# tsl-bt-shield.net
KiCad netlist of a schematic drawn in EAGLE
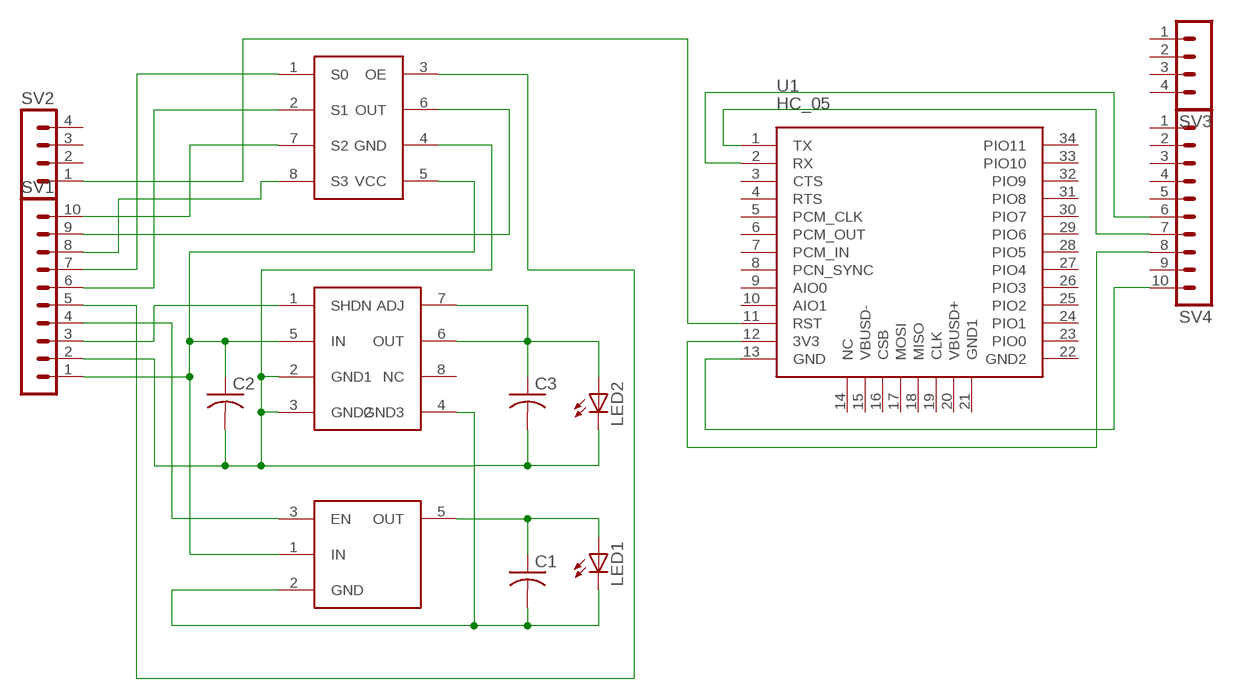
[diagram p0: schematic, sheet 1]

(export (version "E")
  (design (tool "Eeschema 10.0.6"))
  (components
    (comp (ref "C1")
      (value "C-USC1206K")
      (footprint "eagle-import:C1206K")
      (libsource (lib "eagle-import") (part "C-USC1206K"))
    )
    (comp (ref "C2")
      (value "C-USC1206K")
      (footprint "eagle-import:C1206K")
      (libsource (lib "eagle-import") (part "C-USC1206K"))
    )
    (comp (ref "C3")
      (value "C-USC1206K")
      (footprint "eagle-import:C1206K")
      (libsource (lib "eagle-import") (part "C-USC1206K"))
    )
    (comp (ref "LED1")
      (value "LED")
      (footprint "eagle-import:SMARTLED-TTW")
      (libsource (lib "eagle-import") (part "LED"))
    )
    (comp (ref "LED2")
      (value "LED")
      (footprint "eagle-import:SMARTLED-TTW")
      (libsource (lib "eagle-import") (part "LED"))
    )
    (comp (ref "SV1")
      (value "MA10-1")
      (footprint "eagle-import:MA10-1")
      (libsource (lib "eagle-import") (part "MA10-1"))
    )
    (comp (ref "SV2")
      (value "MA04-1")
      (footprint "eagle-import:MA04-1")
      (libsource (lib "eagle-import") (part "MA04-1"))
    )
    (comp (ref "SV3")
      (value "MA04-1")
      (footprint "eagle-import:MA04-1")
      (libsource (lib "eagle-import") (part "MA04-1"))
    )
    (comp (ref "SV4")
      (value "MA10-1")
      (footprint "eagle-import:MA10-1")
      (libsource (lib "eagle-import") (part "MA10-1"))
    )
    (comp (ref "U$1")
      (value "LT3008")
      (footprint "eagle-import:SOT23-8")
      (libsource (lib "eagle-import") (part "LT3008"))
    )
    (comp (ref "U$2")
      (value "TPS7701")
      (footprint "eagle-import:SOT23-5")
      (libsource (lib "eagle-import") (part "TPS7701"))
    )
    (comp (ref "U$3")
      (value "TSL230")
      (footprint "eagle-import:TSL230-SOIC")
      (libsource (lib "eagle-import") (part "TSL230"))
    )
    (comp (ref "U1")
      (value "HC_05")
      (footprint "eagle-import:BLUETOOTH_SMD")
      (libsource (lib "eagle-import") (part "HC_05"))
    )
  )
  (nets
    (net (code "1") (name "Net-(LED1-A)") (class "Default")
      (node (ref "C1") (pin "1") (pinfunction "1_1") (pintype "passive"))
      (node (ref "LED1") (pin "A@1") (pinfunction "A_A@1") (pintype "passive"))
      (node (ref "U$2") (pin "5") (pinfunction "OUT_5") (pintype "bidirectional"))
    )
    (net (code "2") (name "Net-(LED1-C)") (class "Default")
      (node (ref "C1") (pin "2") (pinfunction "2_2") (pintype "passive"))
      (node (ref "C2") (pin "2") (pinfunction "2_2") (pintype "passive"))
      (node (ref "C3") (pin "2") (pinfunction "2_2") (pintype "passive"))
      (node (ref "LED1") (pin "C@1") (pinfunction "C_C@1") (pintype "passive"))
      (node (ref "LED2") (pin "C@1") (pinfunction "C_C@1") (pintype "passive"))
      (node (ref "SV1") (pin "2") (pinfunction "2_2") (pintype "passive"))
      (node (ref "U$1") (pin "2") (pinfunction "GND1_2") (pintype "bidirectional"))
      (node (ref "U$1") (pin "3") (pinfunction "GND2_3") (pintype "bidirectional"))
      (node (ref "U$1") (pin "4") (pinfunction "GND3_4") (pintype "bidirectional"))
      (node (ref "U$2") (pin "2") (pinfunction "GND_2") (pintype "bidirectional"))
      (node (ref "U$3") (pin "4") (pinfunction "GND_4") (pintype "bidirectional"))
    )
    (net (code "3") (name "Net-(LED2-A)") (class "Default")
      (node (ref "C3") (pin "1") (pinfunction "1_1") (pintype "passive"))
      (node (ref "LED2") (pin "A@1") (pinfunction "A_A@1") (pintype "passive"))
      (node (ref "U$1") (pin "6") (pinfunction "OUT_6") (pintype "bidirectional"))
      (node (ref "U$1") (pin "7") (pinfunction "ADJ_7") (pintype "bidirectional"))
    )
    (net (code "4") (name "Net-(U$1-IN)") (class "Default")
      (node (ref "C2") (pin "1") (pinfunction "1_1") (pintype "passive"))
      (node (ref "SV1") (pin "1") (pinfunction "1_1") (pintype "passive"))
      (node (ref "U$1") (pin "5") (pinfunction "IN_5") (pintype "bidirectional"))
      (node (ref "U$2") (pin "1") (pinfunction "IN_1") (pintype "bidirectional"))
      (node (ref "U$3") (pin "5") (pinfunction "VCC_5") (pintype "bidirectional"))
    )
    (net (code "5") (name "Net-(U$1-SHDN)") (class "Default")
      (node (ref "SV1") (pin "3") (pinfunction "3_3") (pintype "passive"))
      (node (ref "U$1") (pin "1") (pinfunction "SHDN_1") (pintype "bidirectional"))
    )
    (net (code "6") (name "Net-(U$2-EN)") (class "Default")
      (node (ref "SV1") (pin "4") (pinfunction "4_4") (pintype "passive"))
      (node (ref "U$2") (pin "3") (pinfunction "EN_3") (pintype "bidirectional"))
    )
    (net (code "7") (name "Net-(U$3-OE)") (class "Default")
      (node (ref "SV1") (pin "5") (pinfunction "5_5") (pintype "passive"))
      (node (ref "U$3") (pin "3") (pinfunction "OE_3") (pintype "bidirectional"))
    )
    (net (code "8") (name "Net-(U$3-OUT)") (class "Default")
      (node (ref "SV1") (pin "9") (pinfunction "9_9") (pintype "passive"))
      (node (ref "U$3") (pin "6") (pinfunction "OUT_6") (pintype "bidirectional"))
    )
    (net (code "9") (name "Net-(U$3-S0)") (class "Default")
      (node (ref "SV1") (pin "7") (pinfunction "7_7") (pintype "passive"))
      (node (ref "U$3") (pin "1") (pinfunction "S0_1") (pintype "bidirectional"))
    )
    (net (code "10") (name "Net-(U$3-S1)") (class "Default")
      (node (ref "SV1") (pin "6") (pinfunction "6_6") (pintype "passive"))
      (node (ref "U$3") (pin "2") (pinfunction "S1_2") (pintype "bidirectional"))
    )
    (net (code "11") (name "Net-(U$3-S2)") (class "Default")
      (node (ref "SV1") (pin "10") (pinfunction "10_10") (pintype "passive"))
      (node (ref "U$3") (pin "7") (pinfunction "S2_7") (pintype "bidirectional"))
    )
    (net (code "12") (name "Net-(U$3-S3)") (class "Default")
      (node (ref "SV1") (pin "8") (pinfunction "8_8") (pintype "passive"))
      (node (ref "U$3") (pin "8") (pinfunction "S3_8") (pintype "bidirectional"))
    )
    (net (code "13") (name "Net-(U1-3V3)") (class "Default")
      (node (ref "SV4") (pin "8") (pinfunction "8_8") (pintype "passive"))
      (node (ref "U1") (pin "12") (pinfunction "3V3_12") (pintype "bidirectional"))
    )
    (net (code "14") (name "Net-(U1-GND)") (class "Default")
      (node (ref "SV4") (pin "10") (pinfunction "10_10") (pintype "passive"))
      (node (ref "U1") (pin "13") (pinfunction "GND_13") (pintype "bidirectional"))
    )
    (net (code "15") (name "Net-(U1-RST)") (class "Default")
      (node (ref "SV2") (pin "1") (pinfunction "1_1") (pintype "passive"))
      (node (ref "U1") (pin "11") (pinfunction "RST_11") (pintype "bidirectional"))
    )
    (net (code "16") (name "Net-(U1-RX)") (class "Default")
      (node (ref "SV4") (pin "6") (pinfunction "6_6") (pintype "passive"))
      (node (ref "U1") (pin "2") (pinfunction "RX_2") (pintype "bidirectional"))
    )
    (net (code "17") (name "Net-(U1-TX)") (class "Default")
      (node (ref "SV4") (pin "7") (pinfunction "7_7") (pintype "passive"))
      (node (ref "U1") (pin "1") (pinfunction "TX_1") (pintype "bidirectional"))
    )
    (net (code "18") (name "unconnected-(SV2-Pad2)") (class "Default")
      (node (ref "SV2") (pin "2") (pinfunction "2_2") (pintype "passive"))
    )
    (net (code "19") (name "unconnected-(SV2-Pad3)") (class "Default")
      (node (ref "SV2") (pin "3") (pinfunction "3_3") (pintype "passive"))
    )
    (net (code "20") (name "unconnected-(SV2-Pad4)") (class "Default")
      (node (ref "SV2") (pin "4") (pinfunction "4_4") (pintype "passive"))
    )
    (net (code "21") (name "unconnected-(SV3-Pad1)") (class "Default")
      (node (ref "SV3") (pin "1") (pinfunction "1_1") (pintype "passive"))
    )
    (net (code "22") (name "unconnected-(SV3-Pad2)") (class "Default")
      (node (ref "SV3") (pin "2") (pinfunction "2_2") (pintype "passive"))
    )
    (net (code "23") (name "unconnected-(SV3-Pad3)") (class "Default")
      (node (ref "SV3") (pin "3") (pinfunction "3_3") (pintype "passive"))
    )
    (net (code "24") (name "unconnected-(SV3-Pad4)") (class "Default")
      (node (ref "SV3") (pin "4") (pinfunction "4_4") (pintype "passive"))
    )
    (net (code "25") (name "unconnected-(SV4-Pad1)") (class "Default")
      (node (ref "SV4") (pin "1") (pinfunction "1_1") (pintype "passive"))
    )
    (net (code "26") (name "unconnected-(SV4-Pad2)") (class "Default")
      (node (ref "SV4") (pin "2") (pinfunction "2_2") (pintype "passive"))
    )
    (net (code "27") (name "unconnected-(SV4-Pad3)") (class "Default")
      (node (ref "SV4") (pin "3") (pinfunction "3_3") (pintype "passive"))
    )
    (net (code "28") (name "unconnected-(SV4-Pad4)") (class "Default")
      (node (ref "SV4") (pin "4") (pinfunction "4_4") (pintype "passive"))
    )
    (net (code "29") (name "unconnected-(SV4-Pad5)") (class "Default")
      (node (ref "SV4") (pin "5") (pinfunction "5_5") (pintype "passive"))
    )
    (net (code "30") (name "unconnected-(SV4-Pad9)") (class "Default")
      (node (ref "SV4") (pin "9") (pinfunction "9_9") (pintype "passive"))
    )
    (net (code "31") (name "unconnected-(U$1-NC-Pad8)") (class "Default")
      (node (ref "U$1") (pin "8") (pinfunction "NC_8") (pintype "bidirectional"))
    )
    (net (code "32") (name "unconnected-(U1-AIO0-Pad9)") (class "Default")
      (node (ref "U1") (pin "9") (pinfunction "AIO0_9") (pintype "bidirectional"))
    )
    (net (code "33") (name "unconnected-(U1-AIO1-Pad10)") (class "Default")
      (node (ref "U1") (pin "10") (pinfunction "AIO1_10") (pintype "bidirectional"))
    )
    (net (code "34") (name "unconnected-(U1-CLK-Pad19)") (class "Default")
      (node (ref "U1") (pin "19") (pinfunction "CLK_19") (pintype "bidirectional"))
    )
    (net (code "35") (name "unconnected-(U1-CSB-Pad16)") (class "Default")
      (node (ref "U1") (pin "16") (pinfunction "CSB_16") (pintype "bidirectional"))
    )
    (net (code "36") (name "unconnected-(U1-CTS-Pad3)") (class "Default")
      (node (ref "U1") (pin "3") (pinfunction "CTS_3") (pintype "bidirectional"))
    )
    (net (code "37") (name "unconnected-(U1-GND1-Pad21)") (class "Default")
      (node (ref "U1") (pin "21") (pinfunction "GND1_21") (pintype "bidirectional"))
    )
    (net (code "38") (name "unconnected-(U1-GND2-Pad22)") (class "Default")
      (node (ref "U1") (pin "22") (pinfunction "GND2_22") (pintype "bidirectional"))
    )
    (net (code "39") (name "unconnected-(U1-MISO-Pad18)") (class "Default")
      (node (ref "U1") (pin "18") (pinfunction "MISO_18") (pintype "bidirectional"))
    )
    (net (code "40") (name "unconnected-(U1-MOSI-Pad17)") (class "Default")
      (node (ref "U1") (pin "17") (pinfunction "MOSI_17") (pintype "bidirectional"))
    )
    (net (code "41") (name "unconnected-(U1-NC-Pad14)") (class "Default")
      (node (ref "U1") (pin "14") (pinfunction "NC_14") (pintype "bidirectional"))
    )
    (net (code "42") (name "unconnected-(U1-PCM_CLK-Pad5)") (class "Default")
      (node (ref "U1") (pin "5") (pinfunction "PCM_CLK_5") (pintype "bidirectional"))
    )
    (net (code "43") (name "unconnected-(U1-PCM_IN-Pad7)") (class "Default")
      (node (ref "U1") (pin "7") (pinfunction "PCM_IN_7") (pintype "bidirectional"))
    )
    (net (code "44") (name "unconnected-(U1-PCM_OUT-Pad6)") (class "Default")
      (node (ref "U1") (pin "6") (pinfunction "PCM_OUT_6") (pintype "bidirectional"))
    )
    (net (code "45") (name "unconnected-(U1-PCN_SYNC-Pad8)") (class "Default")
      (node (ref "U1") (pin "8") (pinfunction "PCN_SYNC_8") (pintype "bidirectional"))
    )
    (net (code "46") (name "unconnected-(U1-PIO0-Pad23)") (class "Default")
      (node (ref "U1") (pin "23") (pinfunction "PIO0_23") (pintype "bidirectional"))
    )
    (net (code "47") (name "unconnected-(U1-PIO1-Pad24)") (class "Default")
      (node (ref "U1") (pin "24") (pinfunction "PIO1_24") (pintype "bidirectional"))
    )
    (net (code "48") (name "unconnected-(U1-PIO2-Pad25)") (class "Default")
      (node (ref "U1") (pin "25") (pinfunction "PIO2_25") (pintype "bidirectional"))
    )
    (net (code "49") (name "unconnected-(U1-PIO3-Pad26)") (class "Default")
      (node (ref "U1") (pin "26") (pinfunction "PIO3_26") (pintype "bidirectional"))
    )
    (net (code "50") (name "unconnected-(U1-PIO4-Pad27)") (class "Default")
      (node (ref "U1") (pin "27") (pinfunction "PIO4_27") (pintype "bidirectional"))
    )
    (net (code "51") (name "unconnected-(U1-PIO5-Pad28)") (class "Default")
      (node (ref "U1") (pin "28") (pinfunction "PIO5_28") (pintype "bidirectional"))
    )
    (net (code "52") (name "unconnected-(U1-PIO6-Pad29)") (class "Default")
      (node (ref "U1") (pin "29") (pinfunction "PIO6_29") (pintype "bidirectional"))
    )
    (net (code "53") (name "unconnected-(U1-PIO7-Pad30)") (class "Default")
      (node (ref "U1") (pin "30") (pinfunction "PIO7_30") (pintype "bidirectional"))
    )
    (net (code "54") (name "unconnected-(U1-PIO8-Pad31)") (class "Default")
      (node (ref "U1") (pin "31") (pinfunction "PIO8_31") (pintype "bidirectional"))
    )
    (net (code "55") (name "unconnected-(U1-PIO9-Pad32)") (class "Default")
      (node (ref "U1") (pin "32") (pinfunction "PIO9_32") (pintype "bidirectional"))
    )
    (net (code "56") (name "unconnected-(U1-PIO10-Pad33)") (class "Default")
      (node (ref "U1") (pin "33") (pinfunction "PIO10_33") (pintype "bidirectional"))
    )
    (net (code "57") (name "unconnected-(U1-PIO11-Pad34)") (class "Default")
      (node (ref "U1") (pin "34") (pinfunction "PIO11_34") (pintype "bidirectional"))
    )
    (net (code "58") (name "unconnected-(U1-RTS-Pad4)") (class "Default")
      (node (ref "U1") (pin "4") (pinfunction "RTS_4") (pintype "bidirectional"))
    )
    (net (code "59") (name "unconnected-(U1-VBUSD+-Pad20)") (class "Default")
      (node (ref "U1") (pin "20") (pinfunction "VBUSD+_20") (pintype "bidirectional"))
    )
    (net (code "60") (name "unconnected-(U1-VBUSD--Pad15)") (class "Default")
      (node (ref "U1") (pin "15") (pinfunction "VBUSD-_15") (pintype "bidirectional"))
    )
  )
)
